# Ch1and2.net
KiCad netlist of a schematic drawn in Altium Designer
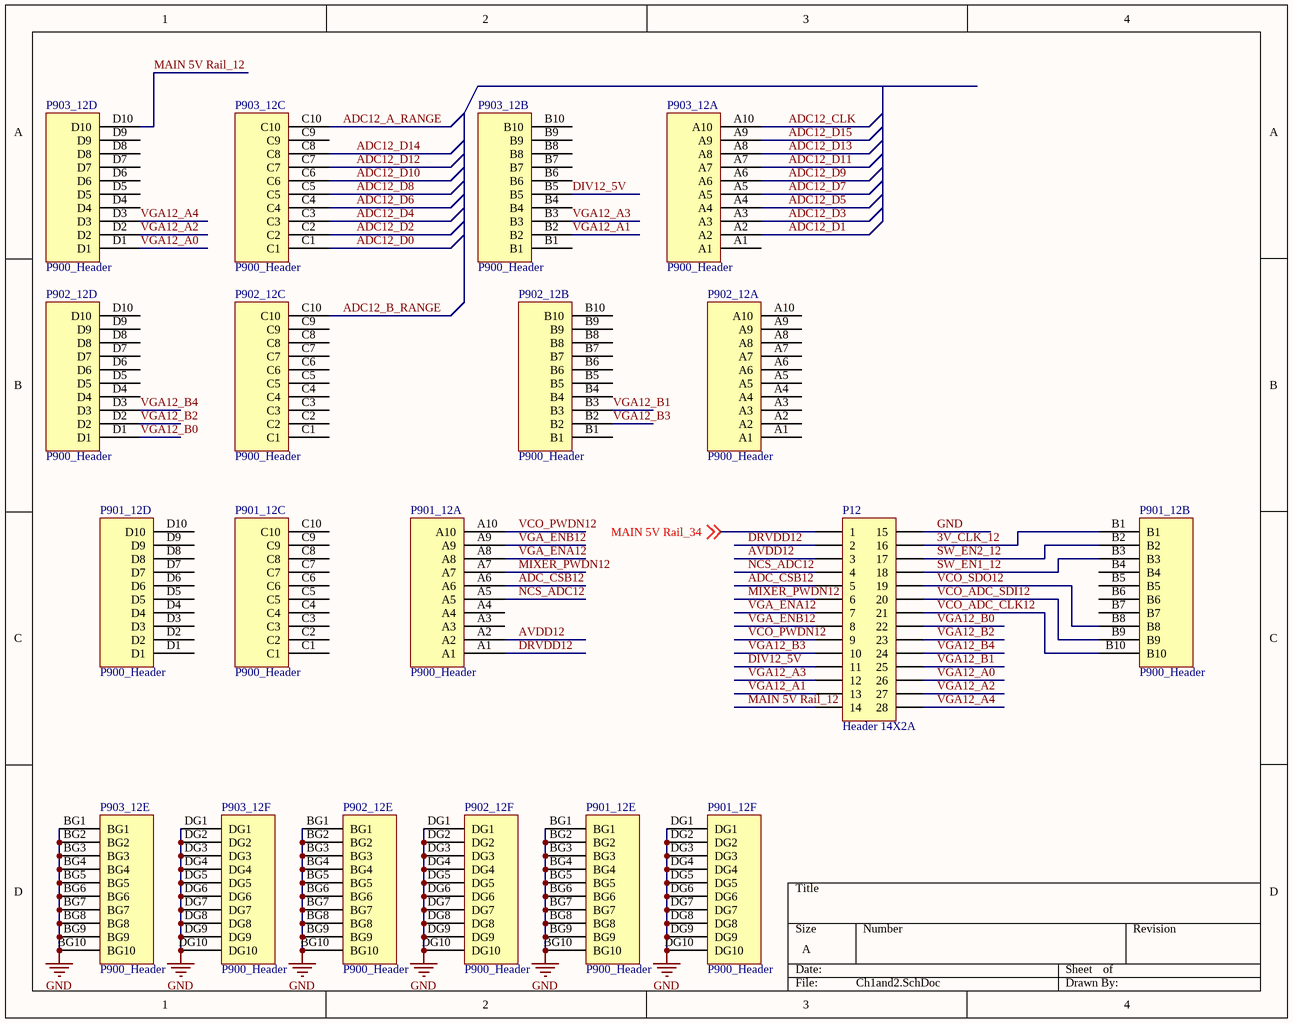
[diagram p0: Ch1and2.SchDoc]

(export (version "E")
  (design (tool "Eeschema 10.0.6"))
  (components
    (comp (ref "P12")
      (value "Header 14X2A")
      (footprint "HDR2X14_CEN")
      (description "Header, 14-Pin, Dual row")
      (fields (field (name "PUBLISHER") "Altium Limited"))
      (libsource (lib "Miscellaneous Connectors") (part "Header 14X2A"))
    )
    (comp (ref "P901_12")
      (value "P900_Header")
      (footprint "P900_header")
      (libsource (lib "") (part "P900_Header_1"))
    )
    (comp (ref "P902_12")
      (value "P900_Header")
      (footprint "P900_header")
      (libsource (lib "MQP_lib") (part "P900_Header"))
    )
    (comp (ref "P903_12")
      (value "P900_Header")
      (footprint "P900_header")
      (libsource (lib "MQP_lib") (part "P900_Header"))
    )
  )
  (nets
    (net (code "1") (name "/3V_CLK_12") (class "Default")
      (node (ref "P12") (pin "16") (pinfunction "16_16") (pintype "passive"))
      (node (ref "P901_12") (pin "B1") (pinfunction "B1_B1") (pintype "passive"))
    )
    (net (code "2") (name "/ADC12_A_RANGE") (class "Default")
      (node (ref "P903_12") (pin "C10") (pinfunction "C10_C10") (pintype "passive"))
    )
    (net (code "3") (name "/ADC12_B_RANGE") (class "Default")
      (node (ref "P902_12") (pin "C10") (pinfunction "C10_C10") (pintype "passive"))
    )
    (net (code "4") (name "/ADC12_CLK") (class "Default")
      (node (ref "P903_12") (pin "A10") (pinfunction "A10_A10") (pintype "passive"))
    )
    (net (code "5") (name "/ADC12_D0") (class "Default")
      (node (ref "P903_12") (pin "C1") (pinfunction "C1_C1") (pintype "passive"))
    )
    (net (code "6") (name "/ADC12_D1") (class "Default")
      (node (ref "P903_12") (pin "A2") (pinfunction "A2_A2") (pintype "passive"))
    )
    (net (code "7") (name "/ADC12_D2") (class "Default")
      (node (ref "P903_12") (pin "C2") (pinfunction "C2_C2") (pintype "passive"))
    )
    (net (code "8") (name "/ADC12_D3") (class "Default")
      (node (ref "P903_12") (pin "A3") (pinfunction "A3_A3") (pintype "passive"))
    )
    (net (code "9") (name "/ADC12_D4") (class "Default")
      (node (ref "P903_12") (pin "C3") (pinfunction "C3_C3") (pintype "passive"))
    )
    (net (code "10") (name "/ADC12_D5") (class "Default")
      (node (ref "P903_12") (pin "A4") (pinfunction "A4_A4") (pintype "passive"))
    )
    (net (code "11") (name "/ADC12_D6") (class "Default")
      (node (ref "P903_12") (pin "C4") (pinfunction "C4_C4") (pintype "passive"))
    )
    (net (code "12") (name "/ADC12_D7") (class "Default")
      (node (ref "P903_12") (pin "A5") (pinfunction "A5_A5") (pintype "passive"))
    )
    (net (code "13") (name "/ADC12_D8") (class "Default")
      (node (ref "P903_12") (pin "C5") (pinfunction "C5_C5") (pintype "passive"))
    )
    (net (code "14") (name "/ADC12_D9") (class "Default")
      (node (ref "P903_12") (pin "A6") (pinfunction "A6_A6") (pintype "passive"))
    )
    (net (code "15") (name "/ADC12_D10") (class "Default")
      (node (ref "P903_12") (pin "C6") (pinfunction "C6_C6") (pintype "passive"))
    )
    (net (code "16") (name "/ADC12_D11") (class "Default")
      (node (ref "P903_12") (pin "A7") (pinfunction "A7_A7") (pintype "passive"))
    )
    (net (code "17") (name "/ADC12_D12") (class "Default")
      (node (ref "P903_12") (pin "C7") (pinfunction "C7_C7") (pintype "passive"))
    )
    (net (code "18") (name "/ADC12_D13") (class "Default")
      (node (ref "P903_12") (pin "A8") (pinfunction "A8_A8") (pintype "passive"))
    )
    (net (code "19") (name "/ADC12_D14") (class "Default")
      (node (ref "P903_12") (pin "C8") (pinfunction "C8_C8") (pintype "passive"))
    )
    (net (code "20") (name "/ADC12_D15") (class "Default")
      (node (ref "P903_12") (pin "A9") (pinfunction "A9_A9") (pintype "passive"))
    )
    (net (code "21") (name "/ADC_CSB12") (class "Default")
      (node (ref "P12") (pin "5") (pinfunction "5_5") (pintype "passive"))
      (node (ref "P901_12") (pin "A6") (pinfunction "A6_A6") (pintype "passive"))
    )
    (net (code "22") (name "/AVDD12") (class "Default")
      (node (ref "P12") (pin "3") (pinfunction "3_3") (pintype "passive"))
      (node (ref "P901_12") (pin "A2") (pinfunction "A2_A2") (pintype "passive"))
    )
    (net (code "23") (name "/DIV12_5V") (class "Default")
      (node (ref "P12") (pin "11") (pinfunction "11_11") (pintype "passive"))
      (node (ref "P903_12") (pin "B5") (pinfunction "B5_B5") (pintype "passive"))
    )
    (net (code "24") (name "/DRVDD12") (class "Default")
      (node (ref "P12") (pin "2") (pinfunction "2_2") (pintype "passive"))
      (node (ref "P901_12") (pin "A1") (pinfunction "A1_A1") (pintype "passive"))
    )
    (net (code "25") (name "/MAIN 5V Rail_12") (class "Default")
      (node (ref "P12") (pin "14") (pinfunction "14_14") (pintype "passive"))
      (node (ref "P903_12") (pin "D10") (pinfunction "D10_D10") (pintype "passive"))
    )
    (net (code "26") (name "/MIXER_PWDN12") (class "Default")
      (node (ref "P12") (pin "6") (pinfunction "6_6") (pintype "passive"))
      (node (ref "P901_12") (pin "A7") (pinfunction "A7_A7") (pintype "passive"))
    )
    (net (code "27") (name "/NCS_ADC12") (class "Default")
      (node (ref "P12") (pin "4") (pinfunction "4_4") (pintype "passive"))
      (node (ref "P901_12") (pin "A5") (pinfunction "A5_A5") (pintype "passive"))
    )
    (net (code "28") (name "/SW_EN1_12") (class "Default")
      (node (ref "P12") (pin "18") (pinfunction "18_18") (pintype "passive"))
      (node (ref "P901_12") (pin "B3") (pinfunction "B3_B3") (pintype "passive"))
    )
    (net (code "29") (name "/SW_EN2_12") (class "Default")
      (node (ref "P12") (pin "17") (pinfunction "17_17") (pintype "passive"))
      (node (ref "P901_12") (pin "B2") (pinfunction "B2_B2") (pintype "passive"))
    )
    (net (code "30") (name "/VCO_ADC_CLK12") (class "Default")
      (node (ref "P12") (pin "21") (pinfunction "21_21") (pintype "passive"))
      (node (ref "P901_12") (pin "B10") (pinfunction "B10_B10") (pintype "passive"))
    )
    (net (code "31") (name "/VCO_ADC_SDI12") (class "Default")
      (node (ref "P12") (pin "20") (pinfunction "20_20") (pintype "passive"))
      (node (ref "P901_12") (pin "B9") (pinfunction "B9_B9") (pintype "passive"))
    )
    (net (code "32") (name "/VCO_PWDN12") (class "Default")
      (node (ref "P12") (pin "9") (pinfunction "9_9") (pintype "passive"))
      (node (ref "P901_12") (pin "A10") (pinfunction "A10_A10") (pintype "passive"))
    )
    (net (code "33") (name "/VCO_SDO12") (class "Default")
      (node (ref "P12") (pin "19") (pinfunction "19_19") (pintype "passive"))
      (node (ref "P901_12") (pin "B8") (pinfunction "B8_B8") (pintype "passive"))
    )
    (net (code "34") (name "/VGA12_A0") (class "Default")
      (node (ref "P12") (pin "26") (pinfunction "26_26") (pintype "passive"))
      (node (ref "P903_12") (pin "D1") (pinfunction "D1_D1") (pintype "passive"))
    )
    (net (code "35") (name "/VGA12_A1") (class "Default")
      (node (ref "P12") (pin "13") (pinfunction "13_13") (pintype "passive"))
      (node (ref "P903_12") (pin "B2") (pinfunction "B2_B2") (pintype "passive"))
    )
    (net (code "36") (name "/VGA12_A2") (class "Default")
      (node (ref "P12") (pin "27") (pinfunction "27_27") (pintype "passive"))
      (node (ref "P903_12") (pin "D2") (pinfunction "D2_D2") (pintype "passive"))
    )
    (net (code "37") (name "/VGA12_A3") (class "Default")
      (node (ref "P12") (pin "12") (pinfunction "12_12") (pintype "passive"))
      (node (ref "P903_12") (pin "B3") (pinfunction "B3_B3") (pintype "passive"))
    )
    (net (code "38") (name "/VGA12_A4") (class "Default")
      (node (ref "P12") (pin "28") (pinfunction "28_28") (pintype "passive"))
      (node (ref "P903_12") (pin "D3") (pinfunction "D3_D3") (pintype "passive"))
    )
    (net (code "39") (name "/VGA12_B0") (class "Default")
      (node (ref "P12") (pin "22") (pinfunction "22_22") (pintype "passive"))
      (node (ref "P902_12") (pin "D1") (pinfunction "D1_D1") (pintype "passive"))
    )
    (net (code "40") (name "/VGA12_B1") (class "Default")
      (node (ref "P12") (pin "25") (pinfunction "25_25") (pintype "passive"))
      (node (ref "P902_12") (pin "B3") (pinfunction "B3_B3") (pintype "passive"))
    )
    (net (code "41") (name "/VGA12_B2") (class "Default")
      (node (ref "P12") (pin "23") (pinfunction "23_23") (pintype "passive"))
      (node (ref "P902_12") (pin "D2") (pinfunction "D2_D2") (pintype "passive"))
    )
    (net (code "42") (name "/VGA12_B3") (class "Default")
      (node (ref "P12") (pin "10") (pinfunction "10_10") (pintype "passive"))
      (node (ref "P902_12") (pin "B2") (pinfunction "B2_B2") (pintype "passive"))
    )
    (net (code "43") (name "/VGA12_B4") (class "Default")
      (node (ref "P12") (pin "24") (pinfunction "24_24") (pintype "passive"))
      (node (ref "P902_12") (pin "D3") (pinfunction "D3_D3") (pintype "passive"))
    )
    (net (code "44") (name "/VGA_ENA12") (class "Default")
      (node (ref "P12") (pin "7") (pinfunction "7_7") (pintype "passive"))
      (node (ref "P901_12") (pin "A8") (pinfunction "A8_A8") (pintype "passive"))
    )
    (net (code "45") (name "/VGA_ENB12") (class "Default")
      (node (ref "P12") (pin "8") (pinfunction "8_8") (pintype "passive"))
      (node (ref "P901_12") (pin "A9") (pinfunction "A9_A9") (pintype "passive"))
    )
    (net (code "46") (name "GND") (class "Default")
      (node (ref "P12") (pin "15") (pinfunction "15_15") (pintype "passive"))
      (node (ref "P901_12") (pin "BG1") (pinfunction "BG1_BG1") (pintype "passive"))
      (node (ref "P901_12") (pin "BG10") (pinfunction "BG10_BG10") (pintype "passive"))
      (node (ref "P901_12") (pin "BG2") (pinfunction "BG2_BG2") (pintype "passive"))
      (node (ref "P901_12") (pin "BG3") (pinfunction "BG3_BG3") (pintype "passive"))
      (node (ref "P901_12") (pin "BG4") (pinfunction "BG4_BG4") (pintype "passive"))
      (node (ref "P901_12") (pin "BG5") (pinfunction "BG5_BG5") (pintype "passive"))
      (node (ref "P901_12") (pin "BG6") (pinfunction "BG6_BG6") (pintype "passive"))
      (node (ref "P901_12") (pin "BG7") (pinfunction "BG7_BG7") (pintype "passive"))
      (node (ref "P901_12") (pin "BG8") (pinfunction "BG8_BG8") (pintype "passive"))
      (node (ref "P901_12") (pin "BG9") (pinfunction "BG9_BG9") (pintype "passive"))
      (node (ref "P901_12") (pin "DG1") (pinfunction "DG1_DG1") (pintype "passive"))
      (node (ref "P901_12") (pin "DG10") (pinfunction "DG10_DG10") (pintype "passive"))
      (node (ref "P901_12") (pin "DG2") (pinfunction "DG2_DG2") (pintype "passive"))
      (node (ref "P901_12") (pin "DG3") (pinfunction "DG3_DG3") (pintype "passive"))
      (node (ref "P901_12") (pin "DG4") (pinfunction "DG4_DG4") (pintype "passive"))
      (node (ref "P901_12") (pin "DG5") (pinfunction "DG5_DG5") (pintype "passive"))
      (node (ref "P901_12") (pin "DG6") (pinfunction "DG6_DG6") (pintype "passive"))
      (node (ref "P901_12") (pin "DG7") (pinfunction "DG7_DG7") (pintype "passive"))
      (node (ref "P901_12") (pin "DG8") (pinfunction "DG8_DG8") (pintype "passive"))
      (node (ref "P901_12") (pin "DG9") (pinfunction "DG9_DG9") (pintype "passive"))
      (node (ref "P902_12") (pin "BG1") (pinfunction "BG1_BG1") (pintype "passive"))
      (node (ref "P902_12") (pin "BG10") (pinfunction "BG10_BG10") (pintype "passive"))
      (node (ref "P902_12") (pin "BG2") (pinfunction "BG2_BG2") (pintype "passive"))
      (node (ref "P902_12") (pin "BG3") (pinfunction "BG3_BG3") (pintype "passive"))
      (node (ref "P902_12") (pin "BG4") (pinfunction "BG4_BG4") (pintype "passive"))
      (node (ref "P902_12") (pin "BG5") (pinfunction "BG5_BG5") (pintype "passive"))
      (node (ref "P902_12") (pin "BG6") (pinfunction "BG6_BG6") (pintype "passive"))
      (node (ref "P902_12") (pin "BG7") (pinfunction "BG7_BG7") (pintype "passive"))
      (node (ref "P902_12") (pin "BG8") (pinfunction "BG8_BG8") (pintype "passive"))
      (node (ref "P902_12") (pin "BG9") (pinfunction "BG9_BG9") (pintype "passive"))
      (node (ref "P902_12") (pin "DG1") (pinfunction "DG1_DG1") (pintype "passive"))
      (node (ref "P902_12") (pin "DG10") (pinfunction "DG10_DG10") (pintype "passive"))
      (node (ref "P902_12") (pin "DG2") (pinfunction "DG2_DG2") (pintype "passive"))
      (node (ref "P902_12") (pin "DG3") (pinfunction "DG3_DG3") (pintype "passive"))
      (node (ref "P902_12") (pin "DG4") (pinfunction "DG4_DG4") (pintype "passive"))
      (node (ref "P902_12") (pin "DG5") (pinfunction "DG5_DG5") (pintype "passive"))
      (node (ref "P902_12") (pin "DG6") (pinfunction "DG6_DG6") (pintype "passive"))
      (node (ref "P902_12") (pin "DG7") (pinfunction "DG7_DG7") (pintype "passive"))
      (node (ref "P902_12") (pin "DG8") (pinfunction "DG8_DG8") (pintype "passive"))
      (node (ref "P902_12") (pin "DG9") (pinfunction "DG9_DG9") (pintype "passive"))
      (node (ref "P903_12") (pin "BG1") (pinfunction "BG1_BG1") (pintype "passive"))
      (node (ref "P903_12") (pin "BG10") (pinfunction "BG10_BG10") (pintype "passive"))
      (node (ref "P903_12") (pin "BG2") (pinfunction "BG2_BG2") (pintype "passive"))
      (node (ref "P903_12") (pin "BG3") (pinfunction "BG3_BG3") (pintype "passive"))
      (node (ref "P903_12") (pin "BG4") (pinfunction "BG4_BG4") (pintype "passive"))
      (node (ref "P903_12") (pin "BG5") (pinfunction "BG5_BG5") (pintype "passive"))
      (node (ref "P903_12") (pin "BG6") (pinfunction "BG6_BG6") (pintype "passive"))
      (node (ref "P903_12") (pin "BG7") (pinfunction "BG7_BG7") (pintype "passive"))
      (node (ref "P903_12") (pin "BG8") (pinfunction "BG8_BG8") (pintype "passive"))
      (node (ref "P903_12") (pin "BG9") (pinfunction "BG9_BG9") (pintype "passive"))
      (node (ref "P903_12") (pin "DG1") (pinfunction "DG1_DG1") (pintype "passive"))
      (node (ref "P903_12") (pin "DG10") (pinfunction "DG10_DG10") (pintype "passive"))
      (node (ref "P903_12") (pin "DG2") (pinfunction "DG2_DG2") (pintype "passive"))
      (node (ref "P903_12") (pin "DG3") (pinfunction "DG3_DG3") (pintype "passive"))
      (node (ref "P903_12") (pin "DG4") (pinfunction "DG4_DG4") (pintype "passive"))
      (node (ref "P903_12") (pin "DG5") (pinfunction "DG5_DG5") (pintype "passive"))
      (node (ref "P903_12") (pin "DG6") (pinfunction "DG6_DG6") (pintype "passive"))
      (node (ref "P903_12") (pin "DG7") (pinfunction "DG7_DG7") (pintype "passive"))
      (node (ref "P903_12") (pin "DG8") (pinfunction "DG8_DG8") (pintype "passive"))
      (node (ref "P903_12") (pin "DG9") (pinfunction "DG9_DG9") (pintype "passive"))
    )
    (net (code "47") (name "MAIN 5V Rail_34") (class "Default")
      (node (ref "P12") (pin "1") (pinfunction "1_1") (pintype "passive"))
    )
    (net (code "48") (name "unconnected-(P901_12-PadA3)") (class "Default")
      (node (ref "P901_12") (pin "A3") (pinfunction "A3_A3") (pintype "passive"))
    )
    (net (code "49") (name "unconnected-(P901_12-PadA4)") (class "Default")
      (node (ref "P901_12") (pin "A4") (pinfunction "A4_A4") (pintype "passive"))
    )
    (net (code "50") (name "unconnected-(P901_12-PadB4)") (class "Default")
      (node (ref "P901_12") (pin "B4") (pinfunction "B4_B4") (pintype "passive"))
    )
    (net (code "51") (name "unconnected-(P901_12-PadB5)") (class "Default")
      (node (ref "P901_12") (pin "B5") (pinfunction "B5_B5") (pintype "passive"))
    )
    (net (code "52") (name "unconnected-(P901_12-PadB6)") (class "Default")
      (node (ref "P901_12") (pin "B6") (pinfunction "B6_B6") (pintype "passive"))
    )
    (net (code "53") (name "unconnected-(P901_12-PadB7)") (class "Default")
      (node (ref "P901_12") (pin "B7") (pinfunction "B7_B7") (pintype "passive"))
    )
    (net (code "54") (name "unconnected-(P901_12-PadC1)") (class "Default")
      (node (ref "P901_12") (pin "C1") (pinfunction "C1_C1") (pintype "passive"))
    )
    (net (code "55") (name "unconnected-(P901_12-PadC2)") (class "Default")
      (node (ref "P901_12") (pin "C2") (pinfunction "C2_C2") (pintype "passive"))
    )
    (net (code "56") (name "unconnected-(P901_12-PadC3)") (class "Default")
      (node (ref "P901_12") (pin "C3") (pinfunction "C3_C3") (pintype "passive"))
    )
    (net (code "57") (name "unconnected-(P901_12-PadC4)") (class "Default")
      (node (ref "P901_12") (pin "C4") (pinfunction "C4_C4") (pintype "passive"))
    )
    (net (code "58") (name "unconnected-(P901_12-PadC5)") (class "Default")
      (node (ref "P901_12") (pin "C5") (pinfunction "C5_C5") (pintype "passive"))
    )
    (net (code "59") (name "unconnected-(P901_12-PadC6)") (class "Default")
      (node (ref "P901_12") (pin "C6") (pinfunction "C6_C6") (pintype "passive"))
    )
    (net (code "60") (name "unconnected-(P901_12-PadC7)") (class "Default")
      (node (ref "P901_12") (pin "C7") (pinfunction "C7_C7") (pintype "passive"))
    )
    (net (code "61") (name "unconnected-(P901_12-PadC8)") (class "Default")
      (node (ref "P901_12") (pin "C8") (pinfunction "C8_C8") (pintype "passive"))
    )
    (net (code "62") (name "unconnected-(P901_12-PadC9)") (class "Default")
      (node (ref "P901_12") (pin "C9") (pinfunction "C9_C9") (pintype "passive"))
    )
    (net (code "63") (name "unconnected-(P901_12-PadC10)") (class "Default")
      (node (ref "P901_12") (pin "C10") (pinfunction "C10_C10") (pintype "passive"))
    )
    (net (code "64") (name "unconnected-(P901_12-PadD1)") (class "Default")
      (node (ref "P901_12") (pin "D1") (pinfunction "D1_D1") (pintype "passive"))
    )
    (net (code "65") (name "unconnected-(P901_12-PadD2)") (class "Default")
      (node (ref "P901_12") (pin "D2") (pinfunction "D2_D2") (pintype "passive"))
    )
    (net (code "66") (name "unconnected-(P901_12-PadD3)") (class "Default")
      (node (ref "P901_12") (pin "D3") (pinfunction "D3_D3") (pintype "passive"))
    )
    (net (code "67") (name "unconnected-(P901_12-PadD4)") (class "Default")
      (node (ref "P901_12") (pin "D4") (pinfunction "D4_D4") (pintype "passive"))
    )
    (net (code "68") (name "unconnected-(P901_12-PadD5)") (class "Default")
      (node (ref "P901_12") (pin "D5") (pinfunction "D5_D5") (pintype "passive"))
    )
    (net (code "69") (name "unconnected-(P901_12-PadD6)") (class "Default")
      (node (ref "P901_12") (pin "D6") (pinfunction "D6_D6") (pintype "passive"))
    )
    (net (code "70") (name "unconnected-(P901_12-PadD7)") (class "Default")
      (node (ref "P901_12") (pin "D7") (pinfunction "D7_D7") (pintype "passive"))
    )
    (net (code "71") (name "unconnected-(P901_12-PadD8)") (class "Default")
      (node (ref "P901_12") (pin "D8") (pinfunction "D8_D8") (pintype "passive"))
    )
    (net (code "72") (name "unconnected-(P901_12-PadD9)") (class "Default")
      (node (ref "P901_12") (pin "D9") (pinfunction "D9_D9") (pintype "passive"))
    )
    (net (code "73") (name "unconnected-(P901_12-PadD10)") (class "Default")
      (node (ref "P901_12") (pin "D10") (pinfunction "D10_D10") (pintype "passive"))
    )
    (net (code "74") (name "unconnected-(P902_12-PadA1)") (class "Default")
      (node (ref "P902_12") (pin "A1") (pinfunction "A1_A1") (pintype "passive"))
    )
    (net (code "75") (name "unconnected-(P902_12-PadA2)") (class "Default")
      (node (ref "P902_12") (pin "A2") (pinfunction "A2_A2") (pintype "passive"))
    )
    (net (code "76") (name "unconnected-(P902_12-PadA3)") (class "Default")
      (node (ref "P902_12") (pin "A3") (pinfunction "A3_A3") (pintype "passive"))
    )
    (net (code "77") (name "unconnected-(P902_12-PadA4)") (class "Default")
      (node (ref "P902_12") (pin "A4") (pinfunction "A4_A4") (pintype "passive"))
    )
    (net (code "78") (name "unconnected-(P902_12-PadA5)") (class "Default")
      (node (ref "P902_12") (pin "A5") (pinfunction "A5_A5") (pintype "passive"))
    )
    (net (code "79") (name "unconnected-(P902_12-PadA6)") (class "Default")
      (node (ref "P902_12") (pin "A6") (pinfunction "A6_A6") (pintype "passive"))
    )
    (net (code "80") (name "unconnected-(P902_12-PadA7)") (class "Default")
      (node (ref "P902_12") (pin "A7") (pinfunction "A7_A7") (pintype "passive"))
    )
    (net (code "81") (name "unconnected-(P902_12-PadA8)") (class "Default")
      (node (ref "P902_12") (pin "A8") (pinfunction "A8_A8") (pintype "passive"))
    )
    (net (code "82") (name "unconnected-(P902_12-PadA9)") (class "Default")
      (node (ref "P902_12") (pin "A9") (pinfunction "A9_A9") (pintype "passive"))
    )
    (net (code "83") (name "unconnected-(P902_12-PadA10)") (class "Default")
      (node (ref "P902_12") (pin "A10") (pinfunction "A10_A10") (pintype "passive"))
    )
    (net (code "84") (name "unconnected-(P902_12-PadB1)") (class "Default")
      (node (ref "P902_12") (pin "B1") (pinfunction "B1_B1") (pintype "passive"))
    )
    (net (code "85") (name "unconnected-(P902_12-PadB4)") (class "Default")
      (node (ref "P902_12") (pin "B4") (pinfunction "B4_B4") (pintype "passive"))
    )
    (net (code "86") (name "unconnected-(P902_12-PadB5)") (class "Default")
      (node (ref "P902_12") (pin "B5") (pinfunction "B5_B5") (pintype "passive"))
    )
    (net (code "87") (name "unconnected-(P902_12-PadB6)") (class "Default")
      (node (ref "P902_12") (pin "B6") (pinfunction "B6_B6") (pintype "passive"))
    )
    (net (code "88") (name "unconnected-(P902_12-PadB7)") (class "Default")
      (node (ref "P902_12") (pin "B7") (pinfunction "B7_B7") (pintype "passive"))
    )
    (net (code "89") (name "unconnected-(P902_12-PadB8)") (class "Default")
      (node (ref "P902_12") (pin "B8") (pinfunction "B8_B8") (pintype "passive"))
    )
    (net (code "90") (name "unconnected-(P902_12-PadB9)") (class "Default")
      (node (ref "P902_12") (pin "B9") (pinfunction "B9_B9") (pintype "passive"))
    )
    (net (code "91") (name "unconnected-(P902_12-PadB10)") (class "Default")
      (node (ref "P902_12") (pin "B10") (pinfunction "B10_B10") (pintype "passive"))
    )
    (net (code "92") (name "unconnected-(P902_12-PadC1)") (class "Default")
      (node (ref "P902_12") (pin "C1") (pinfunction "C1_C1") (pintype "passive"))
    )
    (net (code "93") (name "unconnected-(P902_12-PadC2)") (class "Default")
      (node (ref "P902_12") (pin "C2") (pinfunction "C2_C2") (pintype "passive"))
    )
    (net (code "94") (name "unconnected-(P902_12-PadC3)") (class "Default")
      (node (ref "P902_12") (pin "C3") (pinfunction "C3_C3") (pintype "passive"))
    )
    (net (code "95") (name "unconnected-(P902_12-PadC4)") (class "Default")
      (node (ref "P902_12") (pin "C4") (pinfunction "C4_C4") (pintype "passive"))
    )
    (net (code "96") (name "unconnected-(P902_12-PadC5)") (class "Default")
      (node (ref "P902_12") (pin "C5") (pinfunction "C5_C5") (pintype "passive"))
    )
    (net (code "97") (name "unconnected-(P902_12-PadC6)") (class "Default")
      (node (ref "P902_12") (pin "C6") (pinfunction "C6_C6") (pintype "passive"))
    )
    (net (code "98") (name "unconnected-(P902_12-PadC7)") (class "Default")
      (node (ref "P902_12") (pin "C7") (pinfunction "C7_C7") (pintype "passive"))
    )
    (net (code "99") (name "unconnected-(P902_12-PadC8)") (class "Default")
      (node (ref "P902_12") (pin "C8") (pinfunction "C8_C8") (pintype "passive"))
    )
    (net (code "100") (name "unconnected-(P902_12-PadC9)") (class "Default")
      (node (ref "P902_12") (pin "C9") (pinfunction "C9_C9") (pintype "passive"))
    )
    (net (code "101") (name "unconnected-(P902_12-PadD4)") (class "Default")
      (node (ref "P902_12") (pin "D4") (pinfunction "D4_D4") (pintype "passive"))
    )
    (net (code "102") (name "unconnected-(P902_12-PadD5)") (class "Default")
      (node (ref "P902_12") (pin "D5") (pinfunction "D5_D5") (pintype "passive"))
    )
    (net (code "103") (name "unconnected-(P902_12-PadD6)") (class "Default")
      (node (ref "P902_12") (pin "D6") (pinfunction "D6_D6") (pintype "passive"))
    )
    (net (code "104") (name "unconnected-(P902_12-PadD7)") (class "Default")
      (node (ref "P902_12") (pin "D7") (pinfunction "D7_D7") (pintype "passive"))
    )
    (net (code "105") (name "unconnected-(P902_12-PadD8)") (class "Default")
      (node (ref "P902_12") (pin "D8") (pinfunction "D8_D8") (pintype "passive"))
    )
    (net (code "106") (name "unconnected-(P902_12-PadD9)") (class "Default")
      (node (ref "P902_12") (pin "D9") (pinfunction "D9_D9") (pintype "passive"))
    )
    (net (code "107") (name "unconnected-(P902_12-PadD10)") (class "Default")
      (node (ref "P902_12") (pin "D10") (pinfunction "D10_D10") (pintype "passive"))
    )
    (net (code "108") (name "unconnected-(P903_12-PadA1)") (class "Default")
      (node (ref "P903_12") (pin "A1") (pinfunction "A1_A1") (pintype "passive"))
    )
    (net (code "109") (name "unconnected-(P903_12-PadB1)") (class "Default")
      (node (ref "P903_12") (pin "B1") (pinfunction "B1_B1") (pintype "passive"))
    )
    (net (code "110") (name "unconnected-(P903_12-PadB4)") (class "Default")
      (node (ref "P903_12") (pin "B4") (pinfunction "B4_B4") (pintype "passive"))
    )
    (net (code "111") (name "unconnected-(P903_12-PadB6)") (class "Default")
      (node (ref "P903_12") (pin "B6") (pinfunction "B6_B6") (pintype "passive"))
    )
    (net (code "112") (name "unconnected-(P903_12-PadB7)") (class "Default")
      (node (ref "P903_12") (pin "B7") (pinfunction "B7_B7") (pintype "passive"))
    )
    (net (code "113") (name "unconnected-(P903_12-PadB8)") (class "Default")
      (node (ref "P903_12") (pin "B8") (pinfunction "B8_B8") (pintype "passive"))
    )
    (net (code "114") (name "unconnected-(P903_12-PadB9)") (class "Default")
      (node (ref "P903_12") (pin "B9") (pinfunction "B9_B9") (pintype "passive"))
    )
    (net (code "115") (name "unconnected-(P903_12-PadB10)") (class "Default")
      (node (ref "P903_12") (pin "B10") (pinfunction "B10_B10") (pintype "passive"))
    )
    (net (code "116") (name "unconnected-(P903_12-PadC9)") (class "Default")
      (node (ref "P903_12") (pin "C9") (pinfunction "C9_C9") (pintype "passive"))
    )
    (net (code "117") (name "unconnected-(P903_12-PadD4)") (class "Default")
      (node (ref "P903_12") (pin "D4") (pinfunction "D4_D4") (pintype "passive"))
    )
    (net (code "118") (name "unconnected-(P903_12-PadD5)") (class "Default")
      (node (ref "P903_12") (pin "D5") (pinfunction "D5_D5") (pintype "passive"))
    )
    (net (code "119") (name "unconnected-(P903_12-PadD6)") (class "Default")
      (node (ref "P903_12") (pin "D6") (pinfunction "D6_D6") (pintype "passive"))
    )
    (net (code "120") (name "unconnected-(P903_12-PadD7)") (class "Default")
      (node (ref "P903_12") (pin "D7") (pinfunction "D7_D7") (pintype "passive"))
    )
    (net (code "121") (name "unconnected-(P903_12-PadD8)") (class "Default")
      (node (ref "P903_12") (pin "D8") (pinfunction "D8_D8") (pintype "passive"))
    )
    (net (code "122") (name "unconnected-(P903_12-PadD9)") (class "Default")
      (node (ref "P903_12") (pin "D9") (pinfunction "D9_D9") (pintype "passive"))
    )
  )
)
